# LeafCanV0.net
KiCad netlist of a schematic drawn in EAGLE
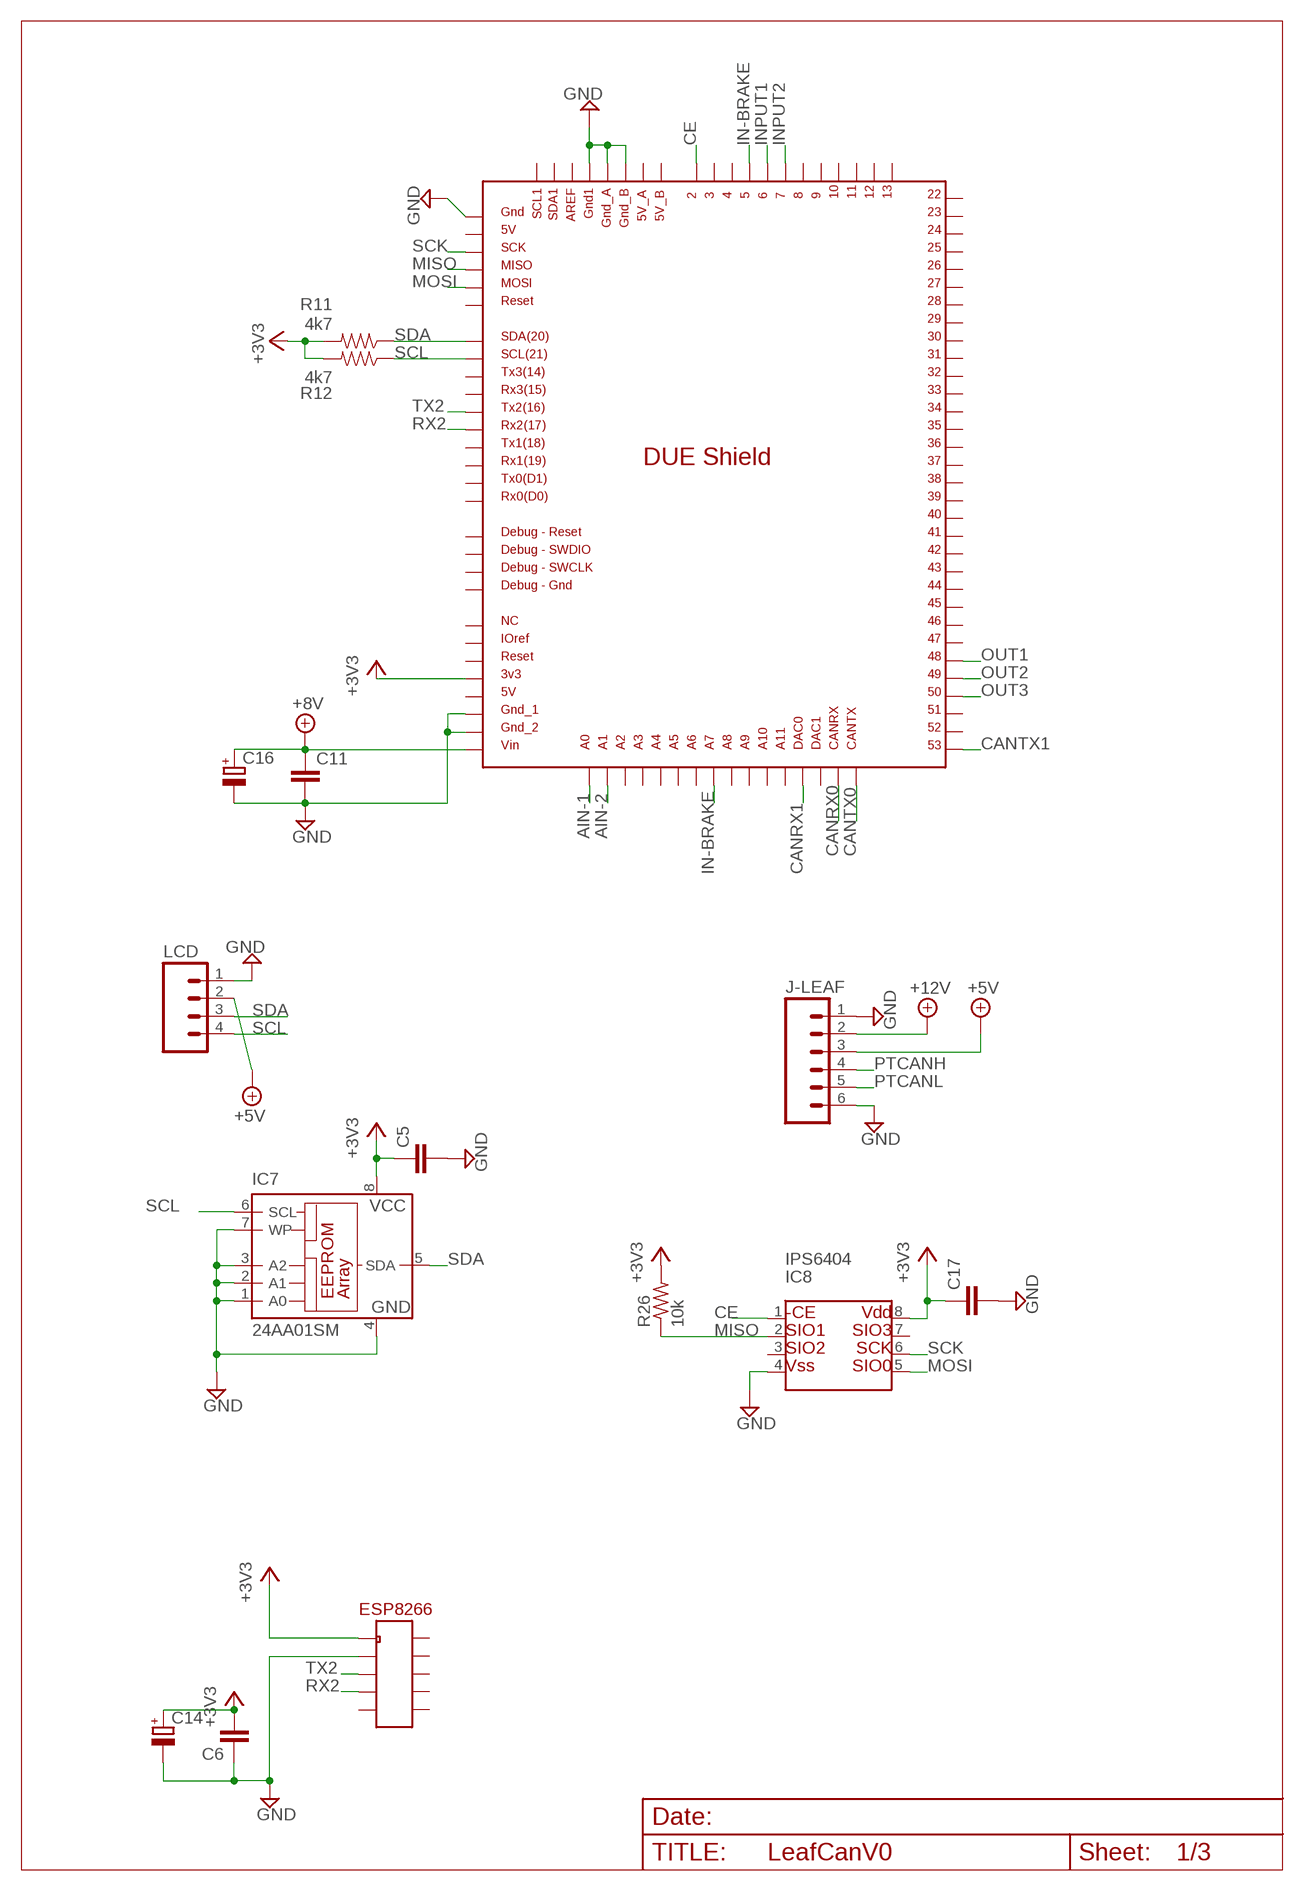
[diagram p0: schematic, sheet 1]
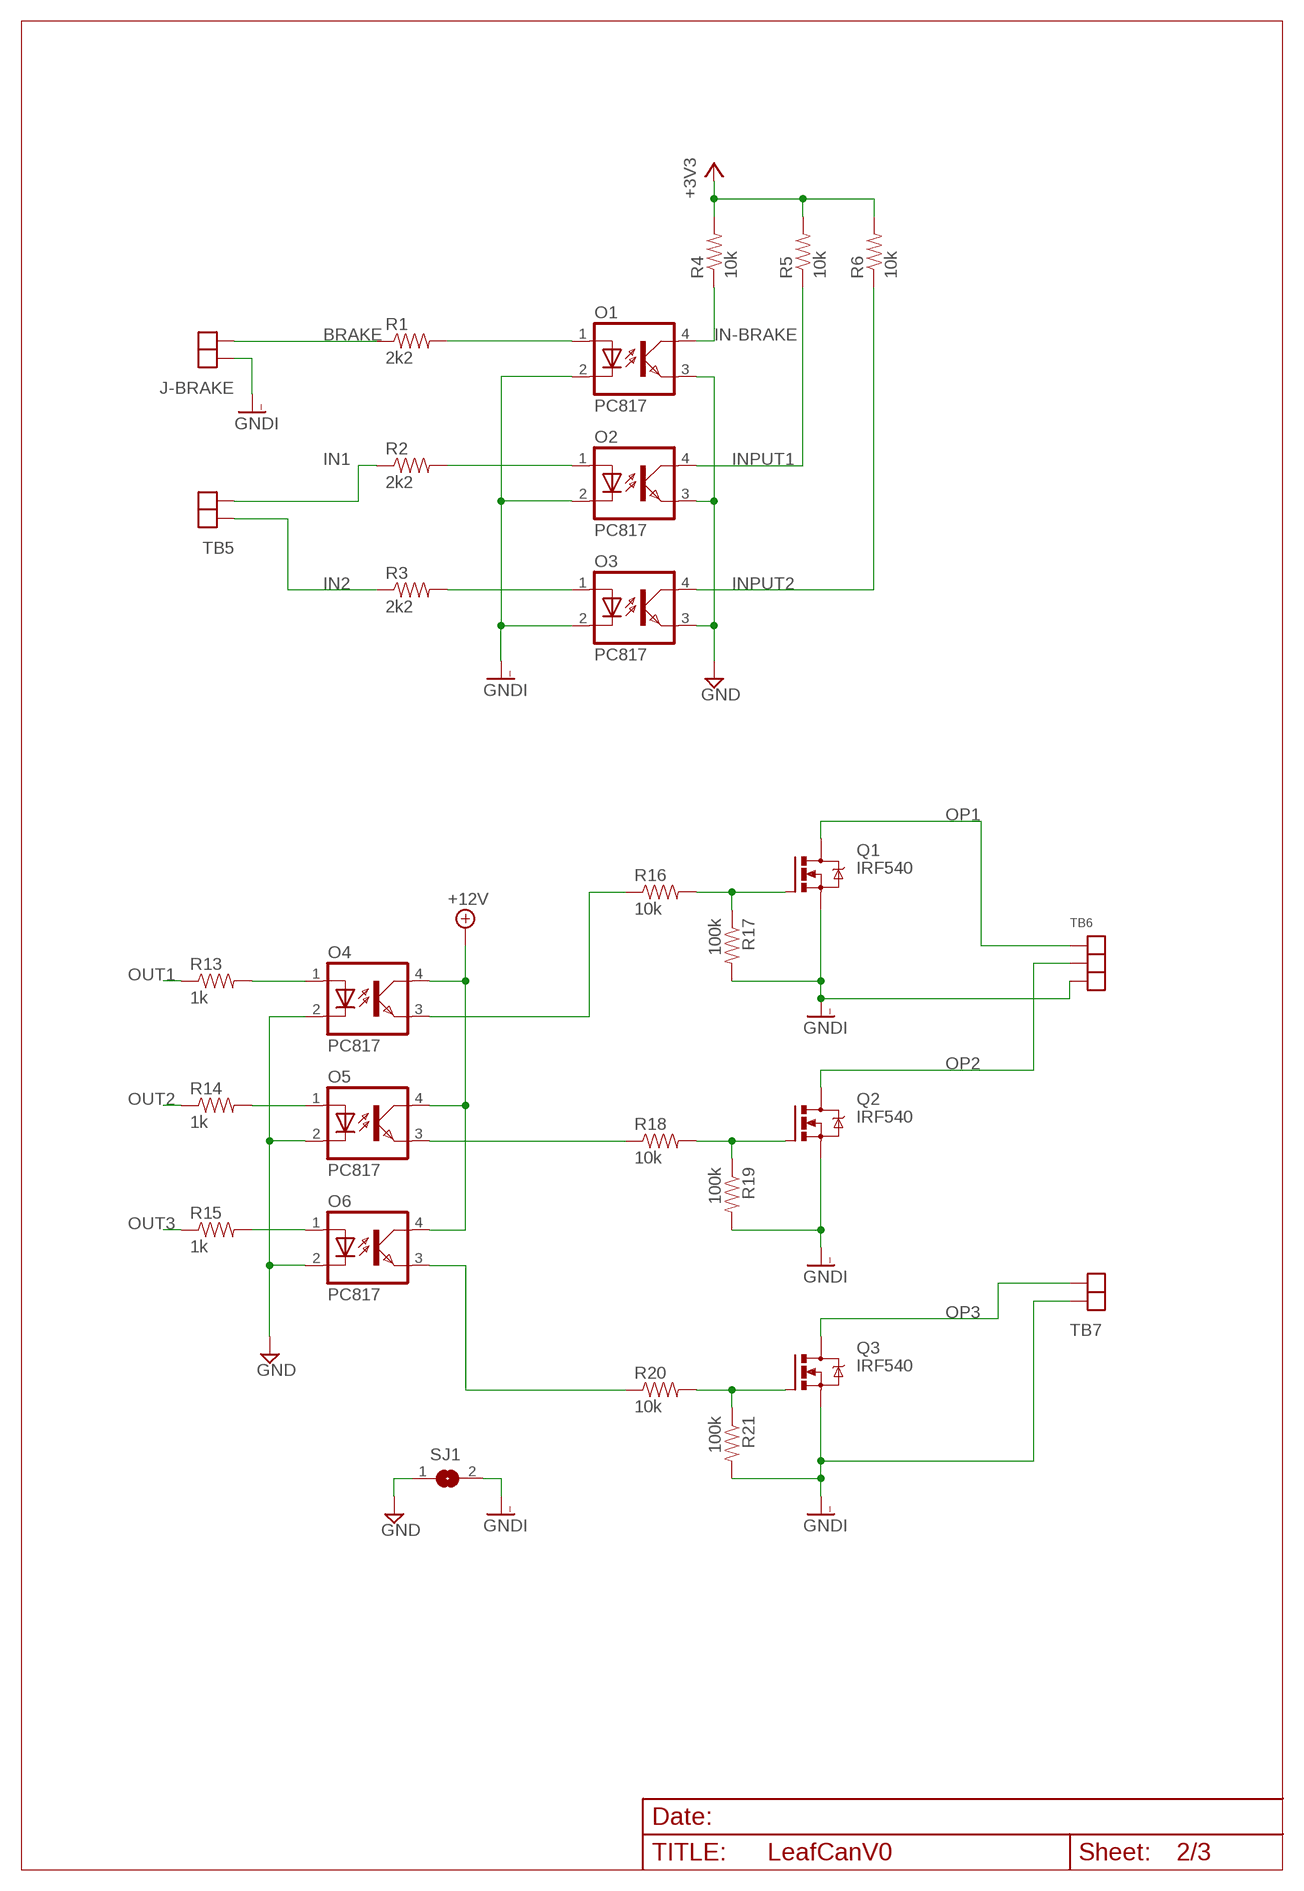
[diagram p1: schematic, sheet 2]
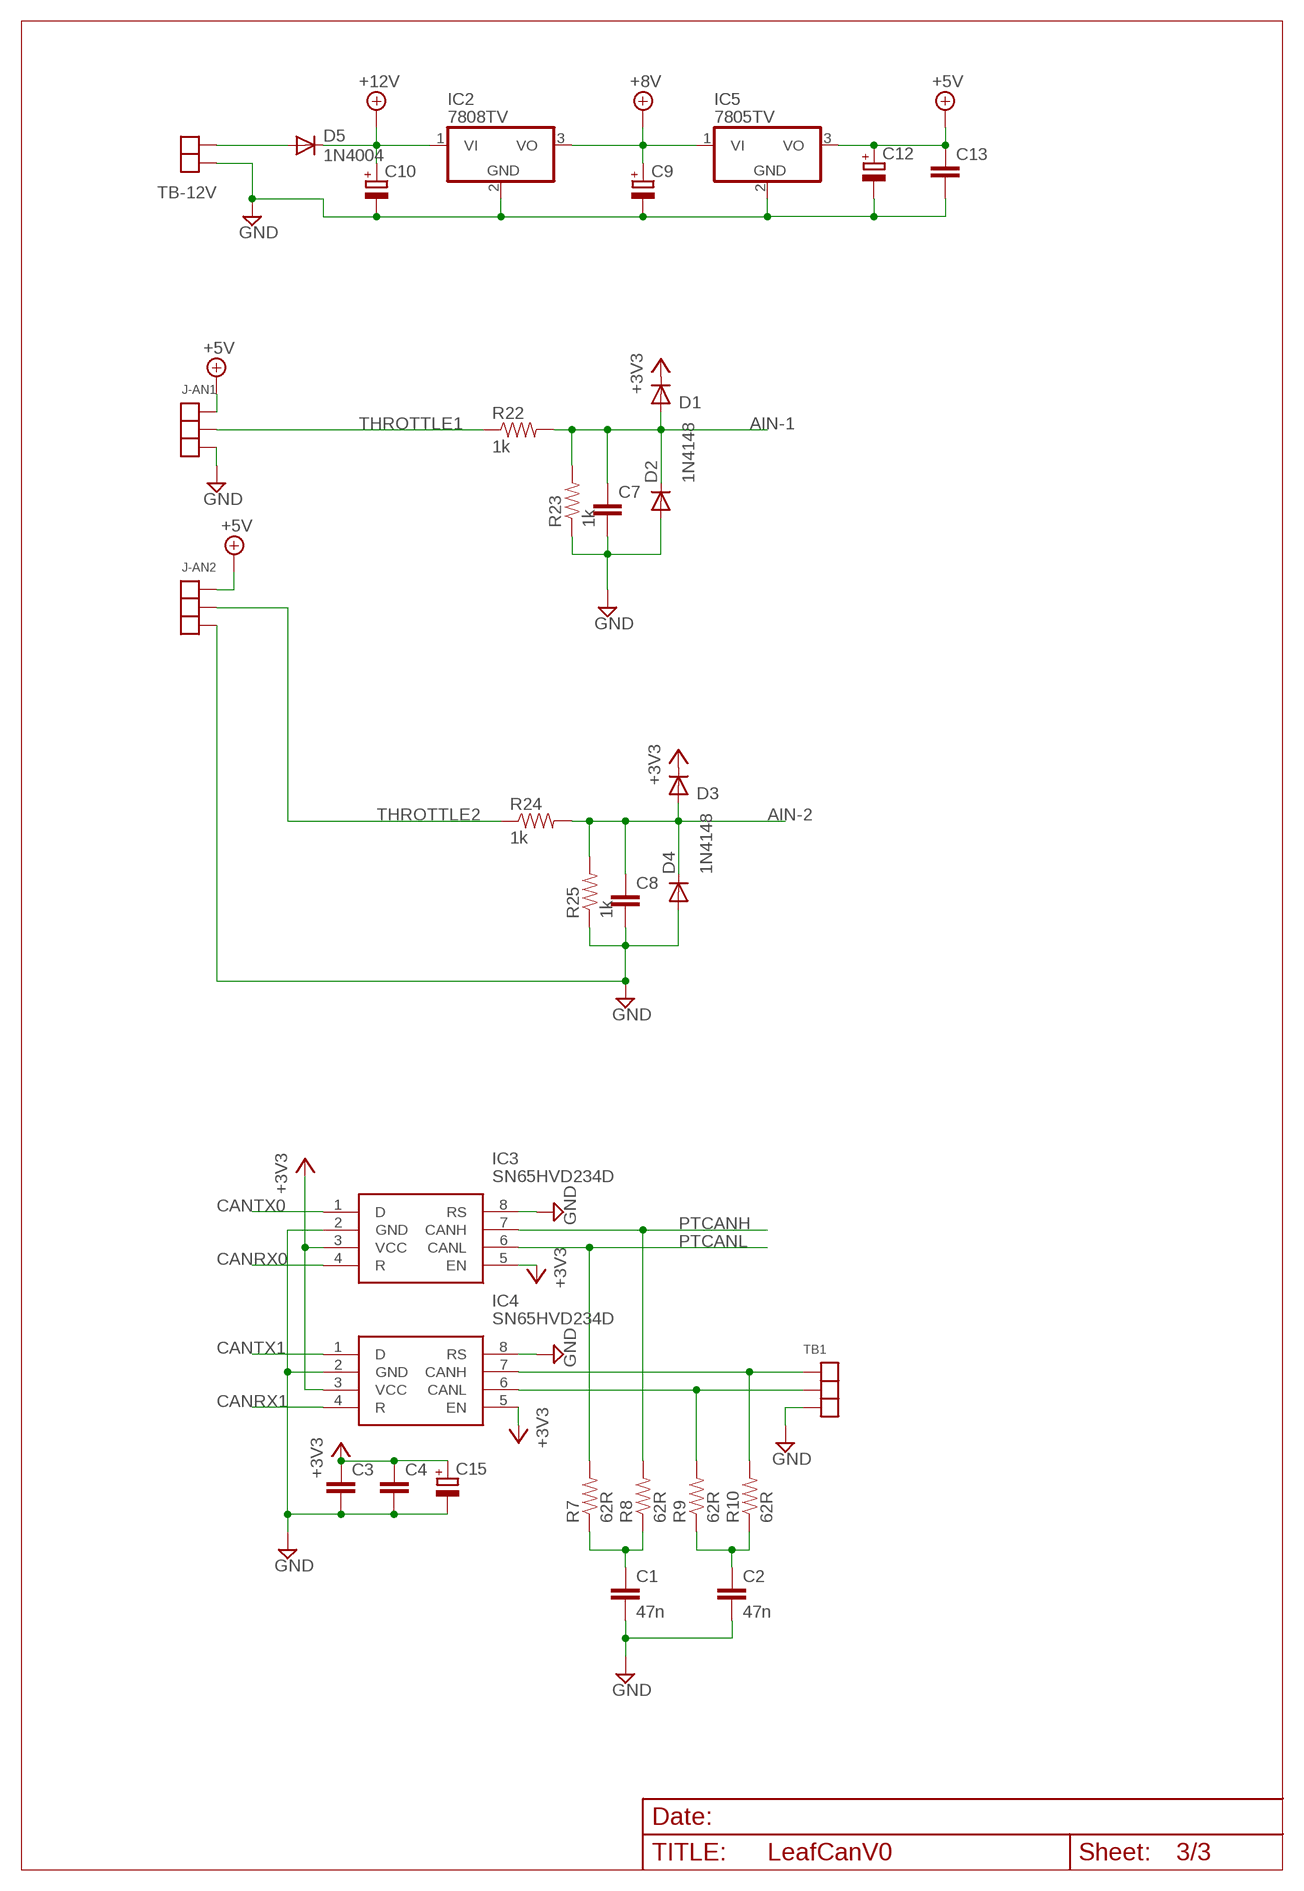
[diagram p2: schematic, sheet 3]

(export (version "E")
  (design (tool "Eeschema 10.0.6"))
  (components
    (comp (ref "C1")
      (value "47n")
      (footprint "eagle-import:C025-030X050")
      (libsource (lib "eagle-import") (part "C-EU025-030X050"))
    )
    (comp (ref "C2")
      (value "47n")
      (footprint "eagle-import:C025-030X050")
      (libsource (lib "eagle-import") (part "C-EU025-030X050"))
    )
    (comp (ref "C3")
      (value "BCAP")
      (footprint "eagle-import:BCAP")
      (libsource (lib "eagle-import") (part "BCAP"))
    )
    (comp (ref "C4")
      (value "BCAP")
      (footprint "eagle-import:BCAP")
      (libsource (lib "eagle-import") (part "BCAP"))
    )
    (comp (ref "C7")
      (value "BCAP")
      (footprint "eagle-import:BCAP")
      (libsource (lib "eagle-import") (part "BCAP"))
    )
    (comp (ref "C8")
      (value "BCAP")
      (footprint "eagle-import:BCAP")
      (libsource (lib "eagle-import") (part "BCAP"))
    )
    (comp (ref "C9")
      (value "C-RB200100")
      (footprint "eagle-import:CPOL-RADIAL-10UF-25V")
      (libsource (lib "eagle-import") (part "C-RB200100"))
    )
    (comp (ref "C10")
      (value "CPOL-EUE7.5-18")
      (footprint "eagle-import:E7,5-18")
      (libsource (lib "eagle-import") (part "CPOL-EUE7.5-18"))
    )
    (comp (ref "C12")
      (value "C-RB200100")
      (footprint "eagle-import:CPOL-RADIAL-10UF-25V")
      (libsource (lib "eagle-import") (part "C-RB200100"))
    )
    (comp (ref "C13")
      (value "BCAP")
      (footprint "eagle-import:BCAP")
      (libsource (lib "eagle-import") (part "BCAP"))
    )
    (comp (ref "C15")
      (value "C-RB200100")
      (footprint "eagle-import:CPOL-RADIAL-10UF-25V")
      (libsource (lib "eagle-import") (part "Andrew Passive_C-RB200100"))
    )
    (comp (ref "D1")
      (value "1N4148")
      (footprint "eagle-import:D3")
      (libsource (lib "eagle-import") (part "1N4148DO35-7"))
    )
    (comp (ref "D2")
      (value "1N4148")
      (footprint "eagle-import:D3")
      (libsource (lib "eagle-import") (part "1N4148DO35-7"))
    )
    (comp (ref "D3")
      (value "1N4148")
      (footprint "eagle-import:D3")
      (libsource (lib "eagle-import") (part "1N4148DO35-7"))
    )
    (comp (ref "D4")
      (value "1N4148")
      (footprint "eagle-import:D3")
      (libsource (lib "eagle-import") (part "1N4148DO35-7"))
    )
    (comp (ref "D5")
      (value "1N4004")
      (footprint "eagle-import:DO41-10")
      (libsource (lib "eagle-import") (part "1N4004"))
    )
    (comp (ref "IC2")
      (value "7808TV")
      (footprint "eagle-import:TO220V")
      (libsource (lib "eagle-import") (part "78TV08"))
    )
    (comp (ref "IC3")
      (value "SN65HVD234D")
      (footprint "eagle-import:SOIC127P600X175-8N")
      (fields
        (field (name "MOUSER_PART_NUMBER") "595-SN65HVD234D")
        (field (name "RS_PART_NUMBER") "6624315P")
      )
      (libsource (lib "eagle-import") (part "SN65HVD234D"))
    )
    (comp (ref "IC4")
      (value "SN65HVD234D")
      (footprint "eagle-import:SOIC127P600X175-8N")
      (fields
        (field (name "MOUSER_PART_NUMBER") "595-SN65HVD234D")
        (field (name "RS_PART_NUMBER") "6624315P")
      )
      (libsource (lib "eagle-import") (part "SN65HVD234D"))
    )
    (comp (ref "IC5")
      (value "7805TV")
      (footprint "eagle-import:TO220V")
      (libsource (lib "eagle-import") (part "78TV05"))
    )
    (comp (ref "J-AN1")
      (value "TB3381V")
      (footprint "eagle-import:TB-KF2EDG381-3-V")
      (libsource (lib "eagle-import") (part "TB3381V"))
    )
    (comp (ref "J-AN2")
      (value "TB3381V")
      (footprint "eagle-import:TB-KF2EDG381-3-V")
      (libsource (lib "eagle-import") (part "TB3381V"))
    )
    (comp (ref "R7")
      (value "62R")
      (footprint "eagle-import:AXIAL-0.4")
      (libsource (lib "eagle-import") (part "R4"))
    )
    (comp (ref "R8")
      (value "62R")
      (footprint "eagle-import:AXIAL-0.4")
      (libsource (lib "eagle-import") (part "R4"))
    )
    (comp (ref "R9")
      (value "62R")
      (footprint "eagle-import:AXIAL-0.4")
      (libsource (lib "eagle-import") (part "R4"))
    )
    (comp (ref "R10")
      (value "62R")
      (footprint "eagle-import:AXIAL-0.4")
      (libsource (lib "eagle-import") (part "R4"))
    )
    (comp (ref "R22")
      (value "1k")
      (footprint "eagle-import:AXIAL-0.4")
      (libsource (lib "eagle-import") (part "R4"))
    )
    (comp (ref "R23")
      (value "1k")
      (footprint "eagle-import:AXIAL-0.4")
      (libsource (lib "eagle-import") (part "R4"))
    )
    (comp (ref "R24")
      (value "1k")
      (footprint "eagle-import:AXIAL-0.4")
      (libsource (lib "eagle-import") (part "R4"))
    )
    (comp (ref "R25")
      (value "1k")
      (footprint "eagle-import:AXIAL-0.4")
      (libsource (lib "eagle-import") (part "R4"))
    )
    (comp (ref "TB-12V")
      (value "TB2381")
      (footprint "eagle-import:TB-KF2EDG381-2P")
      (libsource (lib "eagle-import") (part "TB2381"))
    )
    (comp (ref "TB1")
      (value "TB3381V")
      (footprint "eagle-import:TB-KF2EDG381-3-V")
      (libsource (lib "eagle-import") (part "TB3381V"))
    )
    (comp (ref "J-BRAKE")
      (value "TB2381")
      (footprint "eagle-import:TB-KF2EDG381-2P")
      (libsource (lib "eagle-import") (part "TB2381"))
    )
    (comp (ref "O1")
      (value "PC817")
      (footprint "eagle-import:DIL04")
      (fields (field (name "MPN") "PC817X4J000F"))
      (libsource (lib "eagle-import") (part "PC817"))
    )
    (comp (ref "O2")
      (value "PC817")
      (footprint "eagle-import:DIL04")
      (fields (field (name "MPN") "PC817X4J000F"))
      (libsource (lib "eagle-import") (part "PC817"))
    )
    (comp (ref "O3")
      (value "PC817")
      (footprint "eagle-import:DIL04")
      (fields (field (name "MPN") "PC817X4J000F"))
      (libsource (lib "eagle-import") (part "PC817"))
    )
    (comp (ref "O4")
      (value "PC817")
      (footprint "eagle-import:DIL04")
      (fields (field (name "MPN") "PC817X4J000F"))
      (libsource (lib "eagle-import") (part "PC817"))
    )
    (comp (ref "O5")
      (value "PC817")
      (footprint "eagle-import:DIL04")
      (fields (field (name "MPN") "PC817X4J000F"))
      (libsource (lib "eagle-import") (part "PC817"))
    )
    (comp (ref "O6")
      (value "PC817")
      (footprint "eagle-import:DIL04")
      (fields (field (name "MPN") "PC817X4J000F"))
      (libsource (lib "eagle-import") (part "PC817"))
    )
    (comp (ref "Q1")
      (value "IRF540")
      (footprint "eagle-import:TO220BV")
      (libsource (lib "eagle-import") (part "IRF540"))
    )
    (comp (ref "Q2")
      (value "IRF540")
      (footprint "eagle-import:TO220BV")
      (libsource (lib "eagle-import") (part "IRF540"))
    )
    (comp (ref "Q3")
      (value "IRF540")
      (footprint "eagle-import:TO220BV")
      (libsource (lib "eagle-import") (part "IRF540"))
    )
    (comp (ref "R1")
      (value "2k2")
      (footprint "eagle-import:AXIAL-0.4")
      (libsource (lib "eagle-import") (part "R4"))
    )
    (comp (ref "R2")
      (value "2k2")
      (footprint "eagle-import:AXIAL-0.4")
      (libsource (lib "eagle-import") (part "R4"))
    )
    (comp (ref "R3")
      (value "2k2")
      (footprint "eagle-import:AXIAL-0.4")
      (libsource (lib "eagle-import") (part "R4"))
    )
    (comp (ref "R4")
      (value "10k")
      (footprint "eagle-import:AXIAL-0.4")
      (libsource (lib "eagle-import") (part "R4"))
    )
    (comp (ref "R5")
      (value "10k")
      (footprint "eagle-import:AXIAL-0.4")
      (libsource (lib "eagle-import") (part "R4"))
    )
    (comp (ref "R6")
      (value "10k")
      (footprint "eagle-import:AXIAL-0.4")
      (libsource (lib "eagle-import") (part "R4"))
    )
    (comp (ref "R13")
      (value "1k")
      (footprint "eagle-import:AXIAL-0.4")
      (libsource (lib "eagle-import") (part "R4"))
    )
    (comp (ref "R14")
      (value "1k")
      (footprint "eagle-import:AXIAL-0.4")
      (libsource (lib "eagle-import") (part "R4"))
    )
    (comp (ref "R15")
      (value "1k")
      (footprint "eagle-import:AXIAL-0.4")
      (libsource (lib "eagle-import") (part "R4"))
    )
    (comp (ref "R16")
      (value "10k")
      (footprint "eagle-import:AXIAL-0.4")
      (libsource (lib "eagle-import") (part "R4"))
    )
    (comp (ref "R17")
      (value "100k")
      (footprint "eagle-import:AXIAL-0.4")
      (libsource (lib "eagle-import") (part "R4"))
    )
    (comp (ref "R18")
      (value "10k")
      (footprint "eagle-import:AXIAL-0.4")
      (libsource (lib "eagle-import") (part "R4"))
    )
    (comp (ref "R19")
      (value "100k")
      (footprint "eagle-import:AXIAL-0.4")
      (libsource (lib "eagle-import") (part "R4"))
    )
    (comp (ref "R20")
      (value "10k")
      (footprint "eagle-import:AXIAL-0.4")
      (libsource (lib "eagle-import") (part "R4"))
    )
    (comp (ref "R21")
      (value "100k")
      (footprint "eagle-import:AXIAL-0.4")
      (libsource (lib "eagle-import") (part "R4"))
    )
    (comp (ref "SJ1") (value "SJ") (footprint "eagle-import:SJ") (libsource (lib "eagle-import") (part "SJ")))
    (comp (ref "TB5")
      (value "TB2381")
      (footprint "eagle-import:TB-KF2EDG381-2P")
      (libsource (lib "eagle-import") (part "TB2381"))
    )
    (comp (ref "TB6")
      (value "TB3381")
      (footprint "eagle-import:TB-KF2EDG381-3P")
      (libsource (lib "eagle-import") (part "TB3381"))
    )
    (comp (ref "TB7")
      (value "TB2381")
      (footprint "eagle-import:TB-KF2EDG381-2P")
      (libsource (lib "eagle-import") (part "TB2381"))
    )
    (comp (ref "C5")
      (value "BCAP")
      (footprint "eagle-import:BCAP")
      (libsource (lib "eagle-import") (part "BCAP"))
    )
    (comp (ref "C6")
      (value "BCAP")
      (footprint "eagle-import:BCAP")
      (libsource (lib "eagle-import") (part "BCAP"))
    )
    (comp (ref "C11")
      (value "BCAP")
      (footprint "eagle-import:BCAP")
      (libsource (lib "eagle-import") (part "BCAP"))
    )
    (comp (ref "C14")
      (value "C-RB200100")
      (footprint "eagle-import:CPOL-RADIAL-10UF-25V")
      (libsource (lib "eagle-import") (part "Andrew Passive_C-RB200100"))
    )
    (comp (ref "C16")
      (value "C-RB200100")
      (footprint "eagle-import:CPOL-RADIAL-10UF-25V")
      (libsource (lib "eagle-import") (part "Andrew Passive_C-RB200100"))
    )
    (comp (ref "C17")
      (value "BCAP")
      (footprint "eagle-import:BCAP")
      (libsource (lib "eagle-import") (part "BCAP"))
    )
    (comp (ref "ESP8266")
      (value "IDC10")
      (footprint "eagle-import:IDC10-SMALL")
      (libsource (lib "eagle-import") (part "IDC10"))
    )
    (comp (ref "IC1")
      (value "DUE(NORMAL)")
      (footprint "eagle-import:DUE(NORMAL)")
      (libsource (lib "eagle-import") (part "DUE(NORMAL)"))
    )
    (comp (ref "IC7")
      (value "24AA01SM")
      (footprint "eagle-import:SO-08M")
      (fields (field (name "MF") "MICROCHIP") (field (name "MPN") "24AA01-I/SN"))
      (libsource (lib "eagle-import") (part "24SMAA01"))
    )
    (comp (ref "IC8")
      (value "IPS6404")
      (footprint "eagle-import:SO-08")
      (libsource (lib "eagle-import") (part "IPS6404"))
    )
    (comp (ref "J-LEAF")
      (value "MO6POL")
      (footprint "eagle-import:MOLEX-6")
      (libsource (lib "eagle-import") (part "MO6POL"))
    )
    (comp (ref "LCD")
      (value "MO4POL")
      (footprint "eagle-import:MOLEX-4")
      (libsource (lib "eagle-import") (part "MO4POL"))
    )
    (comp (ref "R11")
      (value "4k7")
      (footprint "eagle-import:AXIAL-0.4")
      (libsource (lib "eagle-import") (part "R4"))
    )
    (comp (ref "R12")
      (value "4k7")
      (footprint "eagle-import:AXIAL-0.4")
      (libsource (lib "eagle-import") (part "R4"))
    )
    (comp (ref "R26")
      (value "10k")
      (footprint "eagle-import:R1206")
      (libsource (lib "eagle-import") (part "R-US_R1206"))
    )
  )
  (nets
    (net (code "1") (name "+3V3") (class "Default")
      (node (ref "C14") (pin "1") (pinfunction "+_1") (pintype "passive"))
      (node (ref "C15") (pin "1") (pinfunction "+_1") (pintype "passive"))
      (node (ref "C17") (pin "1") (pinfunction "1_1") (pintype "passive"))
      (node (ref "C3") (pin "1") (pinfunction "1_1") (pintype "passive"))
      (node (ref "C4") (pin "1") (pinfunction "1_1") (pintype "passive"))
      (node (ref "C5") (pin "1") (pinfunction "1_1") (pintype "passive"))
      (node (ref "C6") (pin "2") (pinfunction "2_2") (pintype "passive"))
      (node (ref "D1") (pin "C") (pinfunction "C_C") (pintype "passive"))
      (node (ref "D3") (pin "C") (pinfunction "C_C") (pintype "passive"))
      (node (ref "ESP8266") (pin "1") (pinfunction "1_1") (pintype "bidirectional"))
      (node (ref "IC1") (pin "3V3") (pinfunction "3V3_3V3") (pintype "bidirectional"))
      (node (ref "IC3") (pin "3") (pinfunction "VCC_3") (pintype "bidirectional"))
      (node (ref "IC3") (pin "5") (pinfunction "EN_5") (pintype "bidirectional"))
      (node (ref "IC4") (pin "3") (pinfunction "VCC_3") (pintype "bidirectional"))
      (node (ref "IC4") (pin "5") (pinfunction "EN_5") (pintype "bidirectional"))
      (node (ref "IC7") (pin "8") (pinfunction "VCC_8") (pintype "power_in"))
      (node (ref "IC8") (pin "8") (pinfunction "P$8_8") (pintype "bidirectional"))
      (node (ref "R11") (pin "P$2") (pinfunction "2_P$2") (pintype "passive"))
      (node (ref "R12") (pin "P$2") (pinfunction "2_P$2") (pintype "passive"))
      (node (ref "R26") (pin "2") (pinfunction "2_2") (pintype "passive"))
      (node (ref "R4") (pin "P$2") (pinfunction "2_P$2") (pintype "passive"))
      (node (ref "R5") (pin "P$2") (pinfunction "2_P$2") (pintype "passive"))
      (node (ref "R6") (pin "P$2") (pinfunction "2_P$2") (pintype "passive"))
    )
    (net (code "2") (name "+5V") (class "Default")
      (node (ref "C12") (pin "1") (pinfunction "+_1") (pintype "passive"))
      (node (ref "C13") (pin "1") (pinfunction "1_1") (pintype "passive"))
      (node (ref "IC5") (pin "3") (pinfunction "VO_3") (pintype "passive"))
      (node (ref "J-AN1") (pin "1") (pinfunction "1_1") (pintype "bidirectional"))
      (node (ref "J-AN2") (pin "1") (pinfunction "1_1") (pintype "bidirectional"))
      (node (ref "J-LEAF") (pin "3") (pinfunction "3_3") (pintype "passive"))
      (node (ref "LCD") (pin "2") (pinfunction "2_2") (pintype "passive"))
    )
    (net (code "3") (name "+8V") (class "Default")
      (node (ref "C11") (pin "1") (pinfunction "1_1") (pintype "passive"))
      (node (ref "C16") (pin "1") (pinfunction "+_1") (pintype "passive"))
      (node (ref "C9") (pin "1") (pinfunction "+_1") (pintype "passive"))
      (node (ref "IC1") (pin "VIN") (pinfunction "VIN_VIN") (pintype "bidirectional"))
      (node (ref "IC2") (pin "3") (pinfunction "VO_3") (pintype "passive"))
      (node (ref "IC5") (pin "1") (pinfunction "VI_1") (pintype "input"))
    )
    (net (code "4") (name "+12V") (class "Default")
      (node (ref "C10") (pin "+") (pinfunction "+_+") (pintype "passive"))
      (node (ref "D5") (pin "C") (pinfunction "C_C") (pintype "passive"))
      (node (ref "IC2") (pin "1") (pinfunction "VI_1") (pintype "input"))
      (node (ref "J-LEAF") (pin "2") (pinfunction "2_2") (pintype "passive"))
      (node (ref "O4") (pin "4") (pinfunction "COL_4") (pintype "passive"))
      (node (ref "O5") (pin "4") (pinfunction "COL_4") (pintype "passive"))
      (node (ref "O6") (pin "4") (pinfunction "COL_4") (pintype "passive"))
    )
    (net (code "5") (name "AIN-1") (class "Default")
      (node (ref "C7") (pin "1") (pinfunction "1_1") (pintype "passive"))
      (node (ref "D1") (pin "A") (pinfunction "A_A") (pintype "passive"))
      (node (ref "D2") (pin "C") (pinfunction "C_C") (pintype "passive"))
      (node (ref "IC1") (pin "A0") (pinfunction "A0_A0") (pintype "bidirectional"))
      (node (ref "R22") (pin "P$2") (pinfunction "2_P$2") (pintype "passive"))
      (node (ref "R23") (pin "P$2") (pinfunction "2_P$2") (pintype "passive"))
    )
    (net (code "6") (name "AIN-2") (class "Default")
      (node (ref "C8") (pin "1") (pinfunction "1_1") (pintype "passive"))
      (node (ref "D3") (pin "A") (pinfunction "A_A") (pintype "passive"))
      (node (ref "D4") (pin "C") (pinfunction "C_C") (pintype "passive"))
      (node (ref "IC1") (pin "A1") (pinfunction "A1_A1") (pintype "bidirectional"))
      (node (ref "R24") (pin "P$2") (pinfunction "2_P$2") (pintype "passive"))
      (node (ref "R25") (pin "P$2") (pinfunction "2_P$2") (pintype "passive"))
    )
    (net (code "7") (name "BRAKE") (class "Default")
      (node (ref "J-BRAKE") (pin "1") (pinfunction "1_1") (pintype "bidirectional"))
      (node (ref "R1") (pin "P$1") (pinfunction "1_P$1") (pintype "passive"))
    )
    (net (code "8") (name "CANRX0") (class "Default")
      (node (ref "IC1") (pin "CANRX") (pinfunction "CANRX_CANRX") (pintype "bidirectional"))
      (node (ref "IC3") (pin "4") (pinfunction "R_4") (pintype "bidirectional"))
    )
    (net (code "9") (name "CANRX1") (class "Default")
      (node (ref "IC1") (pin "DAC0") (pinfunction "DAC0_DAC0") (pintype "bidirectional"))
      (node (ref "IC4") (pin "4") (pinfunction "R_4") (pintype "bidirectional"))
    )
    (net (code "10") (name "CANTX0") (class "Default")
      (node (ref "IC1") (pin "CANTX") (pinfunction "CANTX_CANTX") (pintype "bidirectional"))
      (node (ref "IC3") (pin "1") (pinfunction "D_1") (pintype "bidirectional"))
    )
    (net (code "11") (name "CANTX1") (class "Default")
      (node (ref "IC1") (pin "53") (pinfunction "53_53") (pintype "bidirectional"))
      (node (ref "IC4") (pin "1") (pinfunction "D_1") (pintype "bidirectional"))
    )
    (net (code "12") (name "CE") (class "Default")
      (node (ref "IC1") (pin "2") (pinfunction "2_2") (pintype "bidirectional"))
      (node (ref "IC8") (pin "1") (pinfunction "P$1_1") (pintype "bidirectional"))
    )
    (net (code "13") (name "GND") (class "Default")
      (node (ref "C1") (pin "2") (pinfunction "2_2") (pintype "passive"))
      (node (ref "C10") (pin "-") (pinfunction "-_-") (pintype "passive"))
      (node (ref "C11") (pin "2") (pinfunction "2_2") (pintype "passive"))
      (node (ref "C12") (pin "2") (pinfunction "-_2") (pintype "passive"))
      (node (ref "C13") (pin "2") (pinfunction "2_2") (pintype "passive"))
      (node (ref "C14") (pin "2") (pinfunction "-_2") (pintype "passive"))
      (node (ref "C15") (pin "2") (pinfunction "-_2") (pintype "passive"))
      (node (ref "C16") (pin "2") (pinfunction "-_2") (pintype "passive"))
      (node (ref "C17") (pin "2") (pinfunction "2_2") (pintype "passive"))
      (node (ref "C2") (pin "2") (pinfunction "2_2") (pintype "passive"))
      (node (ref "C3") (pin "2") (pinfunction "2_2") (pintype "passive"))
      (node (ref "C4") (pin "2") (pinfunction "2_2") (pintype "passive"))
      (node (ref "C5") (pin "2") (pinfunction "2_2") (pintype "passive"))
      (node (ref "C6") (pin "1") (pinfunction "1_1") (pintype "passive"))
      (node (ref "C7") (pin "2") (pinfunction "2_2") (pintype "passive"))
      (node (ref "C8") (pin "2") (pinfunction "2_2") (pintype "passive"))
      (node (ref "C9") (pin "2") (pinfunction "-_2") (pintype "passive"))
      (node (ref "D2") (pin "A") (pinfunction "A_A") (pintype "passive"))
      (node (ref "D4") (pin "A") (pinfunction "A_A") (pintype "passive"))
      (node (ref "ESP8266") (pin "3") (pinfunction "3_3") (pintype "bidirectional"))
      (node (ref "IC1") (pin "5V_ICSP") (pinfunction "5V_ICSP_5V_ICSP") (pintype "bidirectional"))
      (node (ref "IC1") (pin "GND1") (pinfunction "GND1_GND1") (pintype "bidirectional"))
      (node (ref "IC1") (pin "GND_1") (pinfunction "GND_1_GND_1") (pintype "bidirectional"))
      (node (ref "IC1") (pin "GND_2") (pinfunction "GND_2_GND_2") (pintype "bidirectional"))
      (node (ref "IC1") (pin "GND_A") (pinfunction "GND_A_GND_A") (pintype "bidirectional"))
      (node (ref "IC1") (pin "GND_B") (pinfunction "GND_B_GND_B") (pintype "bidirectional"))
      (node (ref "IC2") (pin "2") (pinfunction "GND_2") (pintype "passive"))
      (node (ref "IC3") (pin "2") (pinfunction "GND_2") (pintype "bidirectional"))
      (node (ref "IC3") (pin "8") (pinfunction "RS_8") (pintype "bidirectional"))
      (node (ref "IC4") (pin "2") (pinfunction "GND_2") (pintype "bidirectional"))
      (node (ref "IC4") (pin "8") (pinfunction "RS_8") (pintype "bidirectional"))
      (node (ref "IC5") (pin "2") (pinfunction "GND_2") (pintype "passive"))
      (node (ref "IC7") (pin "1") (pinfunction "A0_1") (pintype "input"))
      (node (ref "IC7") (pin "2") (pinfunction "A1_2") (pintype "input"))
      (node (ref "IC7") (pin "3") (pinfunction "A2_3") (pintype "input"))
      (node (ref "IC7") (pin "4") (pinfunction "GND_4") (pintype "power_in"))
      (node (ref "IC7") (pin "7") (pinfunction "WP_7") (pintype "input"))
      (node (ref "IC8") (pin "4") (pinfunction "P$4_4") (pintype "bidirectional"))
      (node (ref "J-AN1") (pin "3") (pinfunction "3_3") (pintype "bidirectional"))
      (node (ref "J-AN2") (pin "3") (pinfunction "3_3") (pintype "bidirectional"))
      (node (ref "J-LEAF") (pin "1") (pinfunction "1_1") (pintype "passive"))
      (node (ref "J-LEAF") (pin "6") (pinfunction "6_6") (pintype "passive"))
      (node (ref "LCD") (pin "1") (pinfunction "1_1") (pintype "passive"))
      (node (ref "O1") (pin "3") (pinfunction "EMIT_3") (pintype "passive"))
      (node (ref "O2") (pin "3") (pinfunction "EMIT_3") (pintype "passive"))
      (node (ref "O3") (pin "3") (pinfunction "EMIT_3") (pintype "passive"))
      (node (ref "O4") (pin "2") (pinfunction "C_2") (pintype "passive"))
      (node (ref "O5") (pin "2") (pinfunction "C_2") (pintype "passive"))
      (node (ref "O6") (pin "2") (pinfunction "C_2") (pintype "passive"))
      (node (ref "R23") (pin "P$1") (pinfunction "1_P$1") (pintype "passive"))
      (node (ref "R25") (pin "P$1") (pinfunction "1_P$1") (pintype "passive"))
      (node (ref "SJ1") (pin "1") (pinfunction "1_1") (pintype "passive"))
      (node (ref "TB-12V") (pin "2") (pinfunction "2_2") (pintype "bidirectional"))
      (node (ref "TB1") (pin "3") (pinfunction "3_3") (pintype "bidirectional"))
    )
    (net (code "14") (name "GNDI") (class "Default")
      (node (ref "J-BRAKE") (pin "2") (pinfunction "2_2") (pintype "bidirectional"))
      (node (ref "O1") (pin "2") (pinfunction "C_2") (pintype "passive"))
      (node (ref "O2") (pin "2") (pinfunction "C_2") (pintype "passive"))
      (node (ref "O3") (pin "2") (pinfunction "C_2") (pintype "passive"))
      (node (ref "Q1") (pin "S") (pinfunction "S_S") (pintype "passive"))
      (node (ref "Q2") (pin "S") (pinfunction "S_S") (pintype "passive"))
      (node (ref "Q3") (pin "S") (pinfunction "S_S") (pintype "passive"))
      (node (ref "R17") (pin "P$2") (pinfunction "2_P$2") (pintype "passive"))
      (node (ref "R19") (pin "P$2") (pinfunction "2_P$2") (pintype "passive"))
      (node (ref "R21") (pin "P$2") (pinfunction "2_P$2") (pintype "passive"))
      (node (ref "SJ1") (pin "2") (pinfunction "2_2") (pintype "passive"))
      (node (ref "TB6") (pin "3") (pinfunction "3_3") (pintype "bidirectional"))
      (node (ref "TB7") (pin "2") (pinfunction "2_2") (pintype "bidirectional"))
    )
    (net (code "15") (name "IN-BRAKE") (class "Default")
      (node (ref "IC1") (pin "5") (pinfunction "5_5") (pintype "bidirectional"))
      (node (ref "IC1") (pin "A7") (pinfunction "A7_A7") (pintype "bidirectional"))
      (node (ref "O1") (pin "4") (pinfunction "COL_4") (pintype "passive"))
      (node (ref "R4") (pin "P$1") (pinfunction "1_P$1") (pintype "passive"))
    )
    (net (code "16") (name "IN1") (class "Default")
      (node (ref "R2") (pin "P$1") (pinfunction "1_P$1") (pintype "passive"))
      (node (ref "TB5") (pin "1") (pinfunction "1_1") (pintype "bidirectional"))
    )
    (net (code "17") (name "IN2") (class "Default")
      (node (ref "R3") (pin "P$1") (pinfunction "1_P$1") (pintype "passive"))
      (node (ref "TB5") (pin "2") (pinfunction "2_2") (pintype "bidirectional"))
    )
    (net (code "18") (name "INPUT1") (class "Default")
      (node (ref "IC1") (pin "6") (pinfunction "6_6") (pintype "bidirectional"))
      (node (ref "O2") (pin "4") (pinfunction "COL_4") (pintype "passive"))
      (node (ref "R5") (pin "P$1") (pinfunction "1_P$1") (pintype "passive"))
    )
    (net (code "19") (name "INPUT2") (class "Default")
      (node (ref "IC1") (pin "7") (pinfunction "7_7") (pintype "bidirectional"))
      (node (ref "O3") (pin "4") (pinfunction "COL_4") (pintype "passive"))
      (node (ref "R6") (pin "P$1") (pinfunction "1_P$1") (pintype "passive"))
    )
    (net (code "20") (name "MISO") (class "Default")
      (node (ref "IC1") (pin "MISO_ICSP") (pinfunction "MISO_ICSP_MISO_ICSP") (pintype "bidirectional"))
      (node (ref "IC8") (pin "2") (pinfunction "P$2_2") (pintype "bidirectional"))
      (node (ref "R26") (pin "1") (pinfunction "1_1") (pintype "passive"))
    )
    (net (code "21") (name "MOSI") (class "Default")
      (node (ref "IC1") (pin "MOSI_ICSP") (pinfunction "MOSI_ICSP_MOSI_ICSP") (pintype "bidirectional"))
      (node (ref "IC8") (pin "5") (pinfunction "P$5_5") (pintype "bidirectional"))
    )
    (net (code "22") (name "Net-(D5-PadA)") (class "Default")
      (node (ref "D5") (pin "A") (pinfunction "A_A") (pintype "passive"))
      (node (ref "TB-12V") (pin "1") (pinfunction "1_1") (pintype "bidirectional"))
    )
    (net (code "23") (name "Net-(IC4-CANH)") (class "Default")
      (node (ref "IC4") (pin "7") (pinfunction "CANH_7") (pintype "bidirectional"))
      (node (ref "R10") (pin "P$2") (pinfunction "2_P$2") (pintype "passive"))
      (node (ref "TB1") (pin "1") (pinfunction "1_1") (pintype "bidirectional"))
    )
    (net (code "24") (name "Net-(IC4-CANL)") (class "Default")
      (node (ref "IC4") (pin "6") (pinfunction "CANL_6") (pintype "bidirectional"))
      (node (ref "R9") (pin "P$2") (pinfunction "2_P$2") (pintype "passive"))
      (node (ref "TB1") (pin "2") (pinfunction "2_2") (pintype "bidirectional"))
    )
    (net (code "25") (name "Net-(O1-A)") (class "Default")
      (node (ref "O1") (pin "1") (pinfunction "A_1") (pintype "passive"))
      (node (ref "R1") (pin "P$2") (pinfunction "2_P$2") (pintype "passive"))
    )
    (net (code "26") (name "Net-(O2-A)") (class "Default")
      (node (ref "O2") (pin "1") (pinfunction "A_1") (pintype "passive"))
      (node (ref "R2") (pin "P$2") (pinfunction "2_P$2") (pintype "passive"))
    )
    (net (code "27") (name "Net-(O3-A)") (class "Default")
      (node (ref "O3") (pin "1") (pinfunction "A_1") (pintype "passive"))
      (node (ref "R3") (pin "P$2") (pinfunction "2_P$2") (pintype "passive"))
    )
    (net (code "28") (name "Net-(O4-A)") (class "Default")
      (node (ref "O4") (pin "1") (pinfunction "A_1") (pintype "passive"))
      (node (ref "R13") (pin "P$2") (pinfunction "2_P$2") (pintype "passive"))
    )
    (net (code "29") (name "Net-(O4-EMIT)") (class "Default")
      (node (ref "O4") (pin "3") (pinfunction "EMIT_3") (pintype "passive"))
      (node (ref "R16") (pin "P$1") (pinfunction "1_P$1") (pintype "passive"))
    )
    (net (code "30") (name "Net-(O5-A)") (class "Default")
      (node (ref "O5") (pin "1") (pinfunction "A_1") (pintype "passive"))
      (node (ref "R14") (pin "P$2") (pinfunction "2_P$2") (pintype "passive"))
    )
    (net (code "31") (name "Net-(O5-EMIT)") (class "Default")
      (node (ref "O5") (pin "3") (pinfunction "EMIT_3") (pintype "passive"))
      (node (ref "R18") (pin "P$1") (pinfunction "1_P$1") (pintype "passive"))
    )
    (net (code "32") (name "Net-(O6-A)") (class "Default")
      (node (ref "O6") (pin "1") (pinfunction "A_1") (pintype "passive"))
      (node (ref "R15") (pin "P$2") (pinfunction "2_P$2") (pintype "passive"))
    )
    (net (code "33") (name "Net-(O6-EMIT)") (class "Default")
      (node (ref "O6") (pin "3") (pinfunction "EMIT_3") (pintype "passive"))
      (node (ref "R20") (pin "P$1") (pinfunction "1_P$1") (pintype "passive"))
    )
    (net (code "34") (name "Net-(R7-1)") (class "Default")
      (node (ref "C1") (pin "1") (pinfunction "1_1") (pintype "passive"))
      (node (ref "R7") (pin "P$1") (pinfunction "1_P$1") (pintype "passive"))
      (node (ref "R8") (pin "P$1") (pinfunction "1_P$1") (pintype "passive"))
    )
    (net (code "35") (name "Net-(R10-1)") (class "Default")
      (node (ref "C2") (pin "1") (pinfunction "1_1") (pintype "passive"))
      (node (ref "R10") (pin "P$1") (pinfunction "1_P$1") (pintype "passive"))
      (node (ref "R9") (pin "P$1") (pinfunction "1_P$1") (pintype "passive"))
    )
    (net (code "36") (name "Net-(R16-2)") (class "Default")
      (node (ref "Q1") (pin "G") (pinfunction "G_G") (pintype "passive"))
      (node (ref "R16") (pin "P$2") (pinfunction "2_P$2") (pintype "passive"))
      (node (ref "R17") (pin "P$1") (pinfunction "1_P$1") (pintype "passive"))
    )
    (net (code "37") (name "Net-(R18-2)") (class "Default")
      (node (ref "Q2") (pin "G") (pinfunction "G_G") (pintype "passive"))
      (node (ref "R18") (pin "P$2") (pinfunction "2_P$2") (pintype "passive"))
      (node (ref "R19") (pin "P$1") (pinfunction "1_P$1") (pintype "passive"))
    )
    (net (code "38") (name "Net-(R20-2)") (class "Default")
      (node (ref "Q3") (pin "G") (pinfunction "G_G") (pintype "passive"))
      (node (ref "R20") (pin "P$2") (pinfunction "2_P$2") (pintype "passive"))
      (node (ref "R21") (pin "P$1") (pinfunction "1_P$1") (pintype "passive"))
    )
    (net (code "39") (name "OP1") (class "Default")
      (node (ref "Q1") (pin "D") (pinfunction "D_D") (pintype "passive"))
      (node (ref "TB6") (pin "1") (pinfunction "1_1") (pintype "bidirectional"))
    )
    (net (code "40") (name "OP2") (class "Default")
      (node (ref "Q2") (pin "D") (pinfunction "D_D") (pintype "passive"))
      (node (ref "TB6") (pin "2") (pinfunction "2_2") (pintype "bidirectional"))
    )
    (net (code "41") (name "OP3") (class "Default")
      (node (ref "Q3") (pin "D") (pinfunction "D_D") (pintype "passive"))
      (node (ref "TB7") (pin "1") (pinfunction "1_1") (pintype "bidirectional"))
    )
    (net (code "42") (name "OUT1") (class "Default")
      (node (ref "IC1") (pin "48") (pinfunction "48_48") (pintype "bidirectional"))
      (node (ref "R13") (pin "P$1") (pinfunction "1_P$1") (pintype "passive"))
    )
    (net (code "43") (name "OUT2") (class "Default")
      (node (ref "IC1") (pin "49") (pinfunction "49_49") (pintype "bidirectional"))
      (node (ref "R14") (pin "P$1") (pinfunction "1_P$1") (pintype "passive"))
    )
    (net (code "44") (name "OUT3") (class "Default")
      (node (ref "IC1") (pin "50") (pinfunction "50_50") (pintype "bidirectional"))
      (node (ref "R15") (pin "P$1") (pinfunction "1_P$1") (pintype "passive"))
    )
    (net (code "45") (name "PTCANH") (class "Default")
      (node (ref "IC3") (pin "7") (pinfunction "CANH_7") (pintype "bidirectional"))
      (node (ref "J-LEAF") (pin "4") (pinfunction "4_4") (pintype "passive"))
      (node (ref "R8") (pin "P$2") (pinfunction "2_P$2") (pintype "passive"))
    )
    (net (code "46") (name "PTCANL") (class "Default")
      (node (ref "IC3") (pin "6") (pinfunction "CANL_6") (pintype "bidirectional"))
      (node (ref "J-LEAF") (pin "5") (pinfunction "5_5") (pintype "passive"))
      (node (ref "R7") (pin "P$2") (pinfunction "2_P$2") (pintype "passive"))
    )
    (net (code "47") (name "RX2") (class "Default")
      (node (ref "ESP8266") (pin "7") (pinfunction "7_7") (pintype "bidirectional"))
      (node (ref "IC1") (pin "RX2") (pinfunction "RX2_RX2") (pintype "bidirectional"))
    )
    (net (code "48") (name "SCK") (class "Default")
      (node (ref "IC1") (pin "SCK_ICSP") (pinfunction "SCK_ICSP_SCK_ICSP") (pintype "bidirectional"))
      (node (ref "IC8") (pin "6") (pinfunction "P$6_6") (pintype "bidirectional"))
    )
    (net (code "49") (name "SCL") (class "Default")
      (node (ref "IC1") (pin "SCL") (pinfunction "SCL_SCL") (pintype "bidirectional"))
      (node (ref "IC7") (pin "6") (pinfunction "SCL_6") (pintype "input"))
      (node (ref "LCD") (pin "4") (pinfunction "4_4") (pintype "passive"))
      (node (ref "R12") (pin "P$1") (pinfunction "1_P$1") (pintype "passive"))
    )
    (net (code "50") (name "SDA") (class "Default")
      (node (ref "IC1") (pin "SDA") (pinfunction "SDA_SDA") (pintype "bidirectional"))
      (node (ref "IC7") (pin "5") (pinfunction "SDA_5") (pintype "bidirectional"))
      (node (ref "LCD") (pin "3") (pinfunction "3_3") (pintype "passive"))
      (node (ref "R11") (pin "P$1") (pinfunction "1_P$1") (pintype "passive"))
    )
    (net (code "51") (name "THROTTLE1") (class "Default")
      (node (ref "J-AN1") (pin "2") (pinfunction "2_2") (pintype "bidirectional"))
      (node (ref "R22") (pin "P$1") (pinfunction "1_P$1") (pintype "passive"))
    )
    (net (code "52") (name "THROTTLE2") (class "Default")
      (node (ref "J-AN2") (pin "2") (pinfunction "2_2") (pintype "bidirectional"))
      (node (ref "R24") (pin "P$1") (pinfunction "1_P$1") (pintype "passive"))
    )
    (net (code "53") (name "TX2") (class "Default")
      (node (ref "ESP8266") (pin "5") (pinfunction "5_5") (pintype "bidirectional"))
      (node (ref "IC1") (pin "TX2") (pinfunction "TX2_TX2") (pintype "bidirectional"))
    )
    (net (code "54") (name "unconnected-(ESP8266-Pad2)") (class "Default")
      (node (ref "ESP8266") (pin "2") (pinfunction "2_2") (pintype "bidirectional"))
    )
    (net (code "55") (name "unconnected-(ESP8266-Pad4)") (class "Default")
      (node (ref "ESP8266") (pin "4") (pinfunction "4_4") (pintype "bidirectional"))
    )
    (net (code "56") (name "unconnected-(ESP8266-Pad6)") (class "Default")
      (node (ref "ESP8266") (pin "6") (pinfunction "6_6") (pintype "bidirectional"))
    )
    (net (code "57") (name "unconnected-(ESP8266-Pad8)") (class "Default")
      (node (ref "ESP8266") (pin "8") (pinfunction "8_8") (pintype "bidirectional"))
    )
    (net (code "58") (name "unconnected-(ESP8266-Pad9)") (class "Default")
      (node (ref "ESP8266") (pin "9") (pinfunction "9_9") (pintype "bidirectional"))
    )
    (net (code "59") (name "unconnected-(ESP8266-Pad10)") (class "Default")
      (node (ref "ESP8266") (pin "10") (pinfunction "10_10") (pintype "bidirectional"))
    )
    (net (code "60") (name "unconnected-(IC1-Pad3)") (class "Default")
      (node (ref "IC1") (pin "3") (pinfunction "3_3") (pintype "bidirectional"))
    )
    (net (code "61") (name "unconnected-(IC1-Pad4)") (class "Default")
      (node (ref "IC1") (pin "4") (pinfunction "4_4") (pintype "bidirectional"))
    )
    (net (code "62") (name "unconnected-(IC1-Pad5V)") (class "Default")
      (node (ref "IC1") (pin "5V") (pinfunction "5V_5V") (pintype "bidirectional"))
    )
    (net (code "63") (name "unconnected-(IC1-Pad5V_A)") (class "Default")
      (node (ref "IC1") (pin "5V_A") (pinfunction "5V_A_5V_A") (pintype "bidirectional"))
    )
    (net (code "64") (name "unconnected-(IC1-Pad5V_B)") (class "Default")
      (node (ref "IC1") (pin "5V_B") (pinfunction "5V_B_5V_B") (pintype "bidirectional"))
    )
    (net (code "65") (name "unconnected-(IC1-Pad8)") (class "Default")
      (node (ref "IC1") (pin "8") (pinfunction "8_8") (pintype "bidirectional"))
    )
    (net (code "66") (name "unconnected-(IC1-Pad9)") (class "Default")
      (node (ref "IC1") (pin "9") (pinfunction "9_9") (pintype "bidirectional"))
    )
    (net (code "67") (name "unconnected-(IC1-Pad10)") (class "Default")
      (node (ref "IC1") (pin "10") (pinfunction "10_10") (pintype "bidirectional"))
    )
    (net (code "68") (name "unconnected-(IC1-Pad11)") (class "Default")
      (node (ref "IC1") (pin "11") (pinfunction "11_11") (pintype "bidirectional"))
    )
    (net (code "69") (name "unconnected-(IC1-Pad12)") (class "Default")
      (node (ref "IC1") (pin "12") (pinfunction "12_12") (pintype "bidirectional"))
    )
    (net (code "70") (name "unconnected-(IC1-Pad13)") (class "Default")
      (node (ref "IC1") (pin "13") (pinfunction "13_13") (pintype "bidirectional"))
    )
    (net (code "71") (name "unconnected-(IC1-Pad22)") (class "Default")
      (node (ref "IC1") (pin "22") (pinfunction "22_22") (pintype "bidirectional"))
    )
    (net (code "72") (name "unconnected-(IC1-Pad23)") (class "Default")
      (node (ref "IC1") (pin "23") (pinfunction "23_23") (pintype "bidirectional"))
    )
    (net (code "73") (name "unconnected-(IC1-Pad24)") (class "Default")
      (node (ref "IC1") (pin "24") (pinfunction "24_24") (pintype "bidirectional"))
    )
    (net (code "74") (name "unconnected-(IC1-Pad25)") (class "Default")
      (node (ref "IC1") (pin "25") (pinfunction "25_25") (pintype "bidirectional"))
    )
    (net (code "75") (name "unconnected-(IC1-Pad26)") (class "Default")
      (node (ref "IC1") (pin "26") (pinfunction "26_26") (pintype "bidirectional"))
    )
    (net (code "76") (name "unconnected-(IC1-Pad27)") (class "Default")
      (node (ref "IC1") (pin "27") (pinfunction "27_27") (pintype "bidirectional"))
    )
    (net (code "77") (name "unconnected-(IC1-Pad28)") (class "Default")
      (node (ref "IC1") (pin "28") (pinfunction "28_28") (pintype "bidirectional"))
    )
    (net (code "78") (name "unconnected-(IC1-Pad29)") (class "Default")
      (node (ref "IC1") (pin "29") (pinfunction "29_29") (pintype "bidirectional"))
    )
    (net (code "79") (name "unconnected-(IC1-Pad30)") (class "Default")
      (node (ref "IC1") (pin "30") (pinfunction "30_30") (pintype "bidirectional"))
    )
    (net (code "80") (name "unconnected-(IC1-Pad31)") (class "Default")
      (node (ref "IC1") (pin "31") (pinfunction "31_31") (pintype "bidirectional"))
    )
    (net (code "81") (name "unconnected-(IC1-Pad32)") (class "Default")
      (node (ref "IC1") (pin "32") (pinfunction "32_32") (pintype "bidirectional"))
    )
    (net (code "82") (name "unconnected-(IC1-Pad33)") (class "Default")
      (node (ref "IC1") (pin "33") (pinfunction "33_33") (pintype "bidirectional"))
    )
    (net (code "83") (name "unconnected-(IC1-Pad34)") (class "Default")
      (node (ref "IC1") (pin "34") (pinfunction "34_34") (pintype "bidirectional"))
    )
    (net (code "84") (name "unconnected-(IC1-Pad35)") (class "Default")
      (node (ref "IC1") (pin "35") (pinfunction "35_35") (pintype "bidirectional"))
    )
    (net (code "85") (name "unconnected-(IC1-Pad36)") (class "Default")
      (node (ref "IC1") (pin "36") (pinfunction "36_36") (pintype "bidirectional"))
    )
    (net (code "86") (name "unconnected-(IC1-Pad37)") (class "Default")
      (node (ref "IC1") (pin "37") (pinfunction "37_37") (pintype "bidirectional"))
    )
    (net (code "87") (name "unconnected-(IC1-Pad38)") (class "Default")
      (node (ref "IC1") (pin "38") (pinfunction "38_38") (pintype "bidirectional"))
    )
    (net (code "88") (name "unconnected-(IC1-Pad39)") (class "Default")
      (node (ref "IC1") (pin "39") (pinfunction "39_39") (pintype "bidirectional"))
    )
    (net (code "89") (name "unconnected-(IC1-Pad40)") (class "Default")
      (node (ref "IC1") (pin "40") (pinfunction "40_40") (pintype "bidirectional"))
    )
    (net (code "90") (name "unconnected-(IC1-Pad41)") (class "Default")
      (node (ref "IC1") (pin "41") (pinfunction "41_41") (pintype "bidirectional"))
    )
    (net (code "91") (name "unconnected-(IC1-Pad42)") (class "Default")
      (node (ref "IC1") (pin "42") (pinfunction "42_42") (pintype "bidirectional"))
    )
    (net (code "92") (name "unconnected-(IC1-Pad43)") (class "Default")
      (node (ref "IC1") (pin "43") (pinfunction "43_43") (pintype "bidirectional"))
    )
    (net (code "93") (name "unconnected-(IC1-Pad44)") (class "Default")
      (node (ref "IC1") (pin "44") (pinfunction "44_44") (pintype "bidirectional"))
    )
    (net (code "94") (name "unconnected-(IC1-Pad45)") (class "Default")
      (node (ref "IC1") (pin "45") (pinfunction "45_45") (pintype "bidirectional"))
    )
    (net (code "95") (name "unconnected-(IC1-Pad46)") (class "Default")
      (node (ref "IC1") (pin "46") (pinfunction "46_46") (pintype "bidirectional"))
    )
    (net (code "96") (name "unconnected-(IC1-Pad47)") (class "Default")
      (node (ref "IC1") (pin "47") (pinfunction "47_47") (pintype "bidirectional"))
    )
    (net (code "97") (name "unconnected-(IC1-Pad51)") (class "Default")
      (node (ref "IC1") (pin "51") (pinfunction "51_51") (pintype "bidirectional"))
    )
    (net (code "98") (name "unconnected-(IC1-Pad52)") (class "Default")
      (node (ref "IC1") (pin "52") (pinfunction "52_52") (pintype "bidirectional"))
    )
    (net (code "99") (name "unconnected-(IC1-PadA2)") (class "Default")
      (node (ref "IC1") (pin "A2") (pinfunction "A2_A2") (pintype "bidirectional"))
    )
    (net (code "100") (name "unconnected-(IC1-PadA3)") (class "Default")
      (node (ref "IC1") (pin "A3") (pinfunction "A3_A3") (pintype "bidirectional"))
    )
    (net (code "101") (name "unconnected-(IC1-PadA4)") (class "Default")
      (node (ref "IC1") (pin "A4") (pinfunction "A4_A4") (pintype "bidirectional"))
    )
    (net (code "102") (name "unconnected-(IC1-PadA5)") (class "Default")
      (node (ref "IC1") (pin "A5") (pinfunction "A5_A5") (pintype "bidirectional"))
    )
    (net (code "103") (name "unconnected-(IC1-PadA6)") (class "Default")
      (node (ref "IC1") (pin "A6") (pinfunction "A6_A6") (pintype "bidirectional"))
    )
    (net (code "104") (name "unconnected-(IC1-PadA8)") (class "Default")
      (node (ref "IC1") (pin "A8") (pinfunction "A8_A8") (pintype "bidirectional"))
    )
    (net (code "105") (name "unconnected-(IC1-PadA9)") (class "Default")
      (node (ref "IC1") (pin "A9") (pinfunction "A9_A9") (pintype "bidirectional"))
    )
    (net (code "106") (name "unconnected-(IC1-PadA10)") (class "Default")
      (node (ref "IC1") (pin "A10") (pinfunction "A10_A10") (pintype "bidirectional"))
    )
    (net (code "107") (name "unconnected-(IC1-PadA11)") (class "Default")
      (node (ref "IC1") (pin "A11") (pinfunction "A11_A11") (pintype "bidirectional"))
    )
    (net (code "108") (name "unconnected-(IC1-PadAREF)") (class "Default")
      (node (ref "IC1") (pin "AREF") (pinfunction "AREF_AREF") (pintype "bidirectional"))
    )
    (net (code "109") (name "unconnected-(IC1-PadDAC1)") (class "Default")
      (node (ref "IC1") (pin "DAC1") (pinfunction "DAC1_DAC1") (pintype "bidirectional"))
    )
    (net (code "110") (name "unconnected-(IC1-PadGND_DEBUG)") (class "Default")
      (node (ref "IC1") (pin "GND_DEBUG") (pinfunction "GND_DEBUG_GND_DEBUG") (pintype "bidirectional"))
    )
    (net (code "111") (name "unconnected-(IC1-PadGND_ICSP)") (class "Default")
      (node (ref "IC1") (pin "GND_ICSP") (pinfunction "GND_ICSP_GND_ICSP") (pintype "bidirectional"))
    )
    (net (code "112") (name "unconnected-(IC1-PadIOREF)") (class "Default")
      (node (ref "IC1") (pin "IOREF") (pinfunction "IOREF_IOREF") (pintype "bidirectional"))
    )
    (net (code "113") (name "unconnected-(IC1-PadNC)") (class "Default")
      (node (ref "IC1") (pin "NC") (pinfunction "NC_NC") (pintype "bidirectional"))
    )
    (net (code "114") (name "unconnected-(IC1-PadRESET)") (class "Default")
      (node (ref "IC1") (pin "RESET") (pinfunction "RESET_RESET") (pintype "bidirectional"))
    )
    (net (code "115") (name "unconnected-(IC1-PadRESET_DEBUG)") (class "Default")
      (node (ref "IC1") (pin "RESET_DEBUG") (pinfunction "RESET_DEBUG_RESET_DEBUG") (pintype "bidirectional"))
    )
    (net (code "116") (name "unconnected-(IC1-PadRESET_ICSP)") (class "Default")
      (node (ref "IC1") (pin "RESET_ICSP") (pinfunction "RESET_ICSP_RESET_ICSP") (pintype "bidirectional"))
    )
    (net (code "117") (name "unconnected-(IC1-PadRX0)") (class "Default")
      (node (ref "IC1") (pin "RX0") (pinfunction "RX0_RX0") (pintype "bidirectional"))
    )
    (net (code "118") (name "unconnected-(IC1-PadRX1)") (class "Default")
      (node (ref "IC1") (pin "RX1") (pinfunction "RX1_RX1") (pintype "bidirectional"))
    )
    (net (code "119") (name "unconnected-(IC1-PadRX3)") (class "Default")
      (node (ref "IC1") (pin "RX3") (pinfunction "RX3_RX3") (pintype "bidirectional"))
    )
    (net (code "120") (name "unconnected-(IC1-PadSCL1)") (class "Default")
      (node (ref "IC1") (pin "SCL1") (pinfunction "SCL1_SCL1") (pintype "bidirectional"))
    )
    (net (code "121") (name "unconnected-(IC1-PadSDA1)") (class "Default")
      (node (ref "IC1") (pin "SDA1") (pinfunction "SDA1_SDA1") (pintype "bidirectional"))
    )
    (net (code "122") (name "unconnected-(IC1-PadSWCLK_DEBUG)") (class "Default")
      (node (ref "IC1") (pin "SWCLK_DEBUG") (pinfunction "SWCLK_DEBUG_SWCLK_DEBUG") (pintype "bidirectional"))
    )
    (net (code "123") (name "unconnected-(IC1-PadSWDIO_DEBUG)") (class "Default")
      (node (ref "IC1") (pin "SWDIO_DEBUG") (pinfunction "SWDIO_DEBUG_SWDIO_DEBUG") (pintype "bidirectional"))
    )
    (net (code "124") (name "unconnected-(IC1-PadTX0)") (class "Default")
      (node (ref "IC1") (pin "TX0") (pinfunction "TX0_TX0") (pintype "bidirectional"))
    )
    (net (code "125") (name "unconnected-(IC1-PadTX1)") (class "Default")
      (node (ref "IC1") (pin "TX1") (pinfunction "TX1_TX1") (pintype "bidirectional"))
    )
    (net (code "126") (name "unconnected-(IC1-PadTX3)") (class "Default")
      (node (ref "IC1") (pin "TX3") (pinfunction "TX3_TX3") (pintype "bidirectional"))
    )
    (net (code "127") (name "unconnected-(IC8-P$3-Pad3)") (class "Default")
      (node (ref "IC8") (pin "3") (pinfunction "P$3_3") (pintype "bidirectional"))
    )
    (net (code "128") (name "unconnected-(IC8-P$7-Pad7)") (class "Default")
      (node (ref "IC8") (pin "7") (pinfunction "P$7_7") (pintype "bidirectional"))
    )
  )
)
